# Backlight.net
KiCad netlist of a schematic drawn in Altium Designer
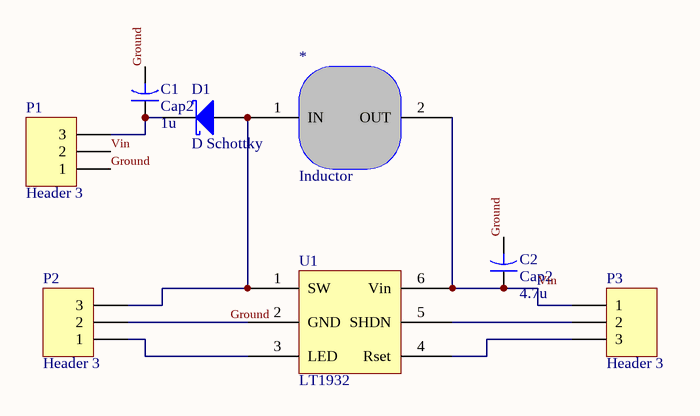
[diagram p0: Backlight.SchDoc]

(export (version "E")
  (design (tool "Eeschema 10.0.6"))
  (components
    (comp (ref "*") (value "Inductor") (footprint "Inductor") (libsource (lib "Parts") (part "Inductor")))
    (comp (ref "C1")
      (value "Cap2")
      (footprint "CAPR5-4X5")
      (description "Capacitor")
      (fields (field (name "ALTIUM_VALUE") "1u") (field (name "PUBLISHER") "Altium Limited"))
      (libsource (lib "Miscellaneous Devices") (part "Cap2"))
    )
    (comp (ref "C2")
      (value "Cap2")
      (footprint "CAPR5-4X5")
      (description "Capacitor")
      (fields (field (name "ALTIUM_VALUE") "4.7u") (field (name "PUBLISHER") "Altium Limited"))
      (libsource (lib "Miscellaneous Devices") (part "Cap2"))
    )
    (comp (ref "D1")
      (value "D Schottky")
      (footprint "RAD-0.2")
      (description "Schottky Diode")
      (fields (field (name "PUBLISHER") "Altium Limited"))
      (libsource (lib "Miscellaneous Devices") (part "D Schottky"))
    )
    (comp (ref "P1")
      (value "Header 3")
      (footprint "HDR1X3")
      (description "Header, 3-Pin")
      (fields (field (name "PUBLISHER") "Altium Limited"))
      (libsource (lib "Miscellaneous Connectors") (part "Header 3"))
    )
    (comp (ref "P2")
      (value "Header 3")
      (footprint "HDR1X3")
      (description "Header, 3-Pin")
      (fields (field (name "PUBLISHER") "Altium Limited"))
      (libsource (lib "Miscellaneous Connectors") (part "Header 3"))
    )
    (comp (ref "P3")
      (value "Header 3")
      (footprint "HDR1X3")
      (description "Header, 3-Pin")
      (fields (field (name "PUBLISHER") "Altium Limited"))
      (libsource (lib "") (part "Header 3_1"))
    )
    (comp (ref "U1") (value "LT1932") (footprint "SOT6") (libsource (lib "Parts") (part "LT1932")))
  )
  (nets
    (net (code "1") (name "/Ground") (class "Default")
      (node (ref "C1") (pin "2") (pinfunction "2_2") (pintype "passive"))
      (node (ref "C2") (pin "2") (pinfunction "2_2") (pintype "passive"))
      (node (ref "P1") (pin "1") (pinfunction "1_1") (pintype "passive"))
      (node (ref "P2") (pin "2") (pinfunction "2_2") (pintype "passive"))
      (node (ref "U1") (pin "2") (pinfunction "GND_2") (pintype "passive"))
    )
    (net (code "2") (name "/Vin") (class "Default")
      (node (ref "*") (pin "2") (pinfunction "OUT_2") (pintype "passive"))
      (node (ref "C2") (pin "1") (pinfunction "1_1") (pintype "passive"))
      (node (ref "P1") (pin "2") (pinfunction "2_2") (pintype "passive"))
      (node (ref "P3") (pin "1") (pinfunction "1_1") (pintype "passive"))
      (node (ref "U1") (pin "6") (pinfunction "Vin_6") (pintype "passive"))
    )
    (net (code "3") (name "Net-(*-IN)") (class "Default")
      (node (ref "*") (pin "1") (pinfunction "IN_1") (pintype "passive"))
      (node (ref "D1") (pin "1") (pinfunction "A_1") (pintype "passive"))
      (node (ref "P2") (pin "3") (pinfunction "3_3") (pintype "passive"))
      (node (ref "U1") (pin "1") (pinfunction "SW_1") (pintype "passive"))
    )
    (net (code "4") (name "Net-(D1-K)") (class "Default")
      (node (ref "C1") (pin "1") (pinfunction "1_1") (pintype "passive"))
      (node (ref "D1") (pin "2") (pinfunction "K_2") (pintype "passive"))
      (node (ref "P1") (pin "3") (pinfunction "3_3") (pintype "passive"))
    )
    (net (code "5") (name "Net-(U1-LED)") (class "Default")
      (node (ref "P2") (pin "1") (pinfunction "1_1") (pintype "passive"))
      (node (ref "U1") (pin "3") (pinfunction "LED_3") (pintype "passive"))
    )
    (net (code "6") (name "Net-(U1-Rset)") (class "Default")
      (node (ref "P3") (pin "3") (pinfunction "3_3") (pintype "passive"))
      (node (ref "U1") (pin "4") (pinfunction "Rset_4") (pintype "passive"))
    )
    (net (code "7") (name "Net-(U1-SHDN)") (class "Default")
      (node (ref "P3") (pin "2") (pinfunction "2_2") (pintype "passive"))
      (node (ref "U1") (pin "5") (pinfunction "SHDN_5") (pintype "passive"))
    )
  )
)
